# IN-12-Arduino-Shield.net
KiCad netlist of a schematic drawn in EAGLE
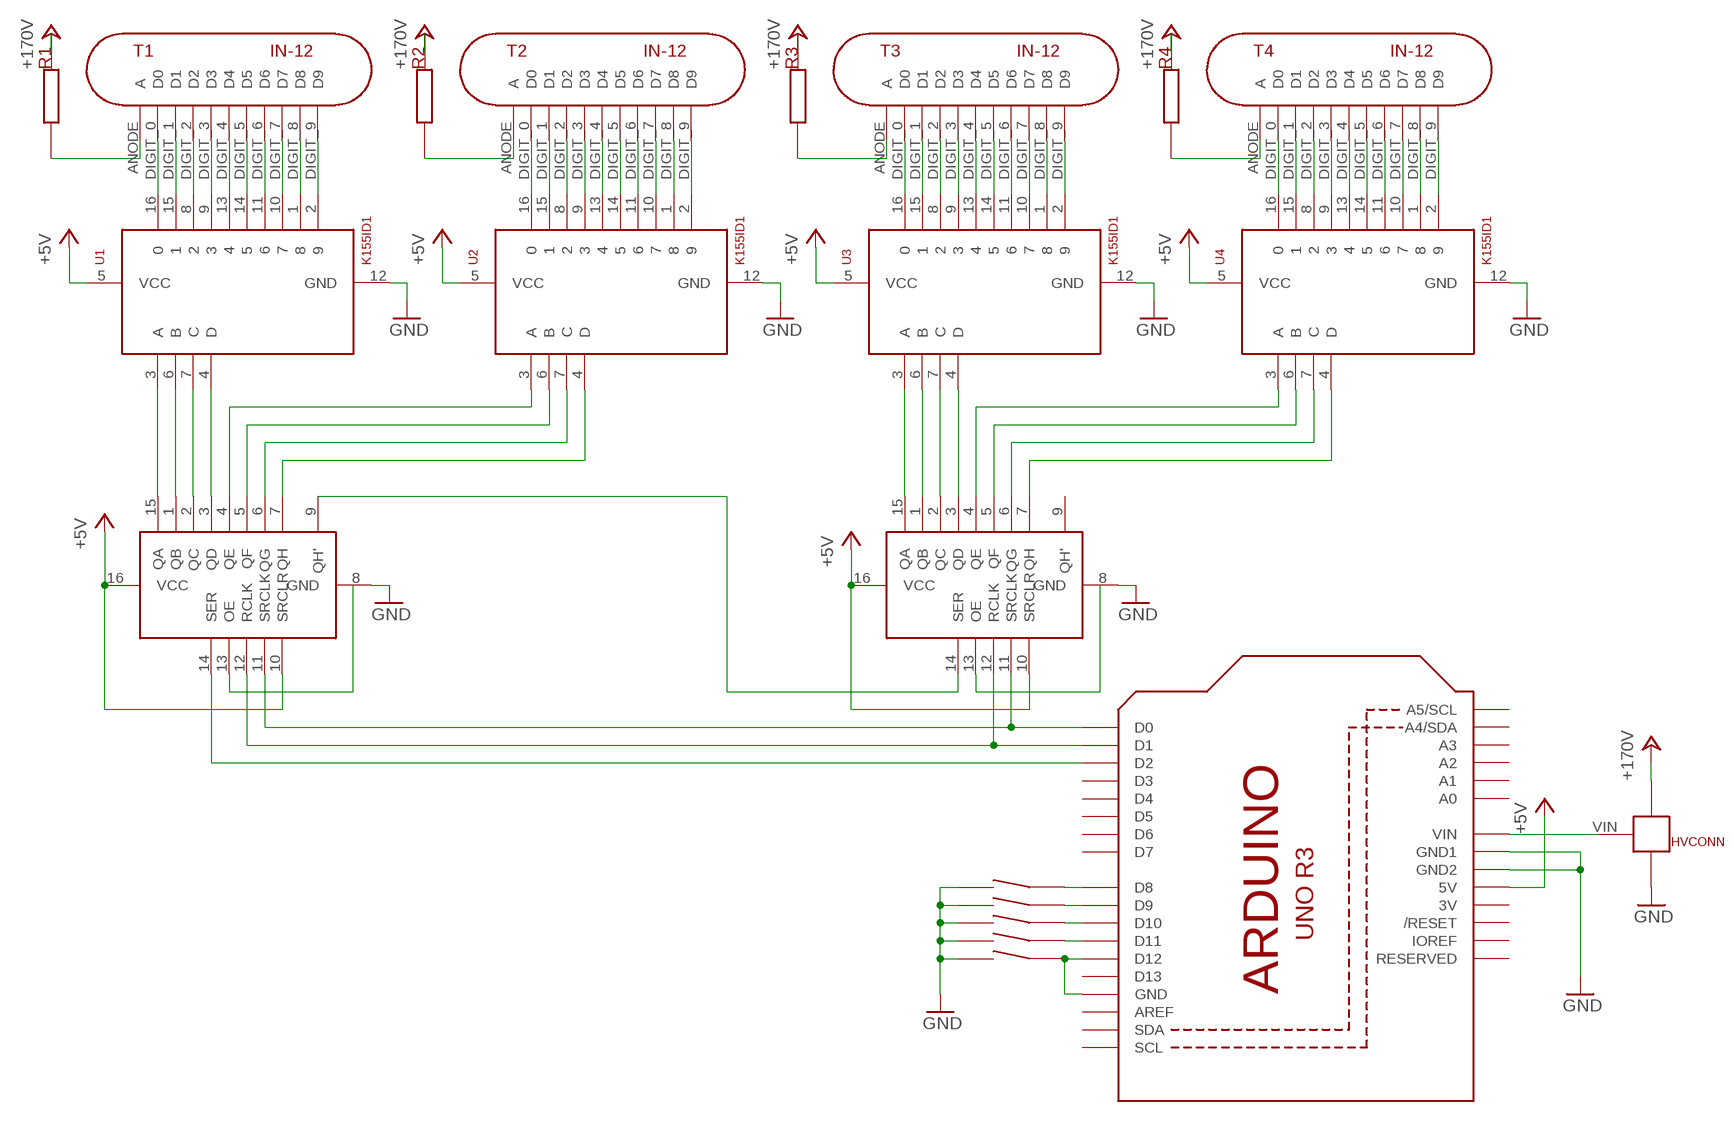
[diagram p0: schematic, sheet 1]

(export (version "E")
  (design (tool "Eeschema 10.0.6"))
  (components
    (comp (ref "HVCONN")
      (value "HV_CONNECTOR")
      (footprint "eagle-import:HV_CONNECTOR")
      (libsource (lib "eagle-import") (part "HV_CONNECTOR"))
    )
    (comp (ref "R1")
      (value "5,6K")
      (footprint "eagle-import:ANODE_RESISTOR")
      (libsource (lib "eagle-import") (part "ANODE_RESISTOR"))
    )
    (comp (ref "R2")
      (value "5,6K")
      (footprint "eagle-import:ANODE_RESISTOR")
      (libsource (lib "eagle-import") (part "ANODE_RESISTOR"))
    )
    (comp (ref "R3")
      (value "5,6K")
      (footprint "eagle-import:ANODE_RESISTOR")
      (libsource (lib "eagle-import") (part "ANODE_RESISTOR"))
    )
    (comp (ref "R4")
      (value "5,6K")
      (footprint "eagle-import:ANODE_RESISTOR")
      (libsource (lib "eagle-import") (part "ANODE_RESISTOR"))
    )
    (comp (ref "T1")
      (value "IN-12")
      (footprint "eagle-import:IN-12")
      (libsource (lib "eagle-import") (part "IN-12"))
    )
    (comp (ref "T2")
      (value "IN-12")
      (footprint "eagle-import:IN-12")
      (libsource (lib "eagle-import") (part "IN-12"))
    )
    (comp (ref "T3")
      (value "IN-12")
      (footprint "eagle-import:IN-12")
      (libsource (lib "eagle-import") (part "IN-12"))
    )
    (comp (ref "T4")
      (value "IN-12")
      (footprint "eagle-import:IN-12")
      (libsource (lib "eagle-import") (part "IN-12"))
    )
    (comp (ref "U$3")
      (value "PUSHBUTTON")
      (footprint "eagle-import:PUSHBUTTON")
      (libsource (lib "eagle-import") (part "PUSHBUTTON"))
    )
    (comp (ref "U$4")
      (value "PUSHBUTTON")
      (footprint "eagle-import:PUSHBUTTON")
      (libsource (lib "eagle-import") (part "PUSHBUTTON"))
    )
    (comp (ref "U$5")
      (value "PUSHBUTTON")
      (footprint "eagle-import:PUSHBUTTON")
      (libsource (lib "eagle-import") (part "PUSHBUTTON"))
    )
    (comp (ref "U$6")
      (value "PUSHBUTTON")
      (footprint "eagle-import:PUSHBUTTON")
      (libsource (lib "eagle-import") (part "PUSHBUTTON"))
    )
    (comp (ref "U$7")
      (value "PUSHBUTTON")
      (footprint "eagle-import:PUSHBUTTON")
      (libsource (lib "eagle-import") (part "PUSHBUTTON"))
    )
    (comp (ref "U1")
      (value "K155ID1")
      (footprint "eagle-import:DIP16-2.54-19.2X7.62MM")
      (libsource (lib "eagle-import") (part "K155ID1"))
    )
    (comp (ref "U2")
      (value "K155ID1")
      (footprint "eagle-import:DIP16-2.54-19.2X7.62MM")
      (libsource (lib "eagle-import") (part "K155ID1"))
    )
    (comp (ref "U3")
      (value "K155ID1")
      (footprint "eagle-import:DIP16-2.54-19.2X7.62MM")
      (libsource (lib "eagle-import") (part "K155ID1"))
    )
    (comp (ref "U4")
      (value "K155ID1")
      (footprint "eagle-import:DIP16-2.54-19.2X7.62MM")
      (libsource (lib "eagle-import") (part "K155ID1"))
    )
    (comp (ref "U5")
      (value "ARDUINOR3")
      (footprint "eagle-import:ARDUINOR3_NO_OUTLINE")
      (libsource (lib "eagle-import") (part "ARDUINOR3"))
    )
    (comp (ref "U6")
      (value "74HC595")
      (footprint "eagle-import:DIL16")
      (libsource (lib "eagle-import") (part "74HC595"))
    )
    (comp (ref "U7")
      (value "74HC595")
      (footprint "eagle-import:DIL16")
      (libsource (lib "eagle-import") (part "74HC595"))
    )
  )
  (nets
    (net (code "1") (name "+5V") (class "Default")
      (node (ref "U1") (pin "5") (pinfunction "VCC_5") (pintype "bidirectional"))
      (node (ref "U2") (pin "5") (pinfunction "VCC_5") (pintype "bidirectional"))
      (node (ref "U3") (pin "5") (pinfunction "VCC_5") (pintype "bidirectional"))
      (node (ref "U4") (pin "5") (pinfunction "VCC_5") (pintype "bidirectional"))
      (node (ref "U5") (pin "5V") (pinfunction "5V_5V") (pintype "power_in"))
      (node (ref "U6") (pin "10") (pinfunction "SRCLR_10") (pintype "bidirectional"))
      (node (ref "U6") (pin "16") (pinfunction "VCC_16") (pintype "bidirectional"))
      (node (ref "U7") (pin "10") (pinfunction "SRCLR_10") (pintype "bidirectional"))
      (node (ref "U7") (pin "16") (pinfunction "VCC_16") (pintype "bidirectional"))
    )
    (net (code "2") (name "+170V") (class "Default")
      (node (ref "HVCONN") (pin "+170V") (pinfunction "P$1_+170V") (pintype "bidirectional"))
      (node (ref "R1") (pin "P$2") (pinfunction "P$2_P$2") (pintype "bidirectional"))
      (node (ref "R2") (pin "P$2") (pinfunction "P$2_P$2") (pintype "bidirectional"))
      (node (ref "R3") (pin "P$2") (pinfunction "P$2_P$2") (pintype "bidirectional"))
      (node (ref "R4") (pin "P$2") (pinfunction "P$2_P$2") (pintype "bidirectional"))
    )
    (net (code "3") (name "/3V") (class "Default")
      (node (ref "U5") (pin "3V") (pinfunction "3V_3V") (pintype "power_in"))
    )
    (net (code "4") (name "GND") (class "Default")
      (node (ref "HVCONN") (pin "GND") (pinfunction "P$2_GND") (pintype "bidirectional"))
      (node (ref "U$3") (pin "P$1") (pinfunction "P$1_P$1") (pintype "bidirectional"))
      (node (ref "U$4") (pin "P$1") (pinfunction "P$1_P$1") (pintype "bidirectional"))
      (node (ref "U$5") (pin "P$1") (pinfunction "P$1_P$1") (pintype "bidirectional"))
      (node (ref "U$6") (pin "P$1") (pinfunction "P$1_P$1") (pintype "bidirectional"))
      (node (ref "U$7") (pin "P$1") (pinfunction "P$1_P$1") (pintype "bidirectional"))
      (node (ref "U1") (pin "12") (pinfunction "GND_12") (pintype "bidirectional"))
      (node (ref "U2") (pin "12") (pinfunction "GND_12") (pintype "bidirectional"))
      (node (ref "U3") (pin "12") (pinfunction "GND_12") (pintype "bidirectional"))
      (node (ref "U4") (pin "12") (pinfunction "GND_12") (pintype "bidirectional"))
      (node (ref "U5") (pin "GND1") (pinfunction "GND1_GND1") (pintype "power_in"))
      (node (ref "U5") (pin "GND2") (pinfunction "GND2_GND2") (pintype "power_in"))
      (node (ref "U6") (pin "8") (pinfunction "GND_8") (pintype "bidirectional"))
      (node (ref "U7") (pin "8") (pinfunction "GND_8") (pintype "bidirectional"))
    )
    (net (code "5") (name "Net-(HVCONN-PadVIN)") (class "Default")
      (node (ref "HVCONN") (pin "VIN") (pinfunction "VIN_VIN") (pintype "bidirectional"))
      (node (ref "U5") (pin "VIN") (pinfunction "VIN_VIN") (pintype "power_in"))
    )
    (net (code "6") (name "Net-(T1-A)") (class "Default")
      (node (ref "R1") (pin "P$1") (pinfunction "P$1_P$1") (pintype "bidirectional"))
      (node (ref "T1") (pin "ANODE") (pinfunction "A_ANODE") (pintype "bidirectional"))
    )
    (net (code "7") (name "Net-(T1-D0)") (class "Default")
      (node (ref "T1") (pin "DIGIT_0") (pinfunction "D0_DIGIT_0") (pintype "bidirectional"))
      (node (ref "U1") (pin "16") (pinfunction "0_16") (pintype "bidirectional"))
    )
    (net (code "8") (name "Net-(T1-D1)") (class "Default")
      (node (ref "T1") (pin "DIGIT_1") (pinfunction "D1_DIGIT_1") (pintype "bidirectional"))
      (node (ref "U1") (pin "15") (pinfunction "1_15") (pintype "bidirectional"))
    )
    (net (code "9") (name "Net-(T1-D2)") (class "Default")
      (node (ref "T1") (pin "DIGIT_2") (pinfunction "D2_DIGIT_2") (pintype "bidirectional"))
      (node (ref "U1") (pin "8") (pinfunction "2_8") (pintype "bidirectional"))
    )
    (net (code "10") (name "Net-(T1-D3)") (class "Default")
      (node (ref "T1") (pin "DIGIT_3") (pinfunction "D3_DIGIT_3") (pintype "bidirectional"))
      (node (ref "U1") (pin "9") (pinfunction "3_9") (pintype "bidirectional"))
    )
    (net (code "11") (name "Net-(T1-D4)") (class "Default")
      (node (ref "T1") (pin "DIGIT_4") (pinfunction "D4_DIGIT_4") (pintype "bidirectional"))
      (node (ref "U1") (pin "13") (pinfunction "4_13") (pintype "bidirectional"))
    )
    (net (code "12") (name "Net-(T1-D5)") (class "Default")
      (node (ref "T1") (pin "DIGIT_5") (pinfunction "D5_DIGIT_5") (pintype "bidirectional"))
      (node (ref "U1") (pin "14") (pinfunction "5_14") (pintype "bidirectional"))
    )
    (net (code "13") (name "Net-(T1-D6)") (class "Default")
      (node (ref "T1") (pin "DIGIT_6") (pinfunction "D6_DIGIT_6") (pintype "bidirectional"))
      (node (ref "U1") (pin "11") (pinfunction "6_11") (pintype "bidirectional"))
    )
    (net (code "14") (name "Net-(T1-D7)") (class "Default")
      (node (ref "T1") (pin "DIGIT_7") (pinfunction "D7_DIGIT_7") (pintype "bidirectional"))
      (node (ref "U1") (pin "10") (pinfunction "7_10") (pintype "bidirectional"))
    )
    (net (code "15") (name "Net-(T1-D8)") (class "Default")
      (node (ref "T1") (pin "DIGIT_8") (pinfunction "D8_DIGIT_8") (pintype "bidirectional"))
      (node (ref "U1") (pin "1") (pinfunction "8_1") (pintype "bidirectional"))
    )
    (net (code "16") (name "Net-(T1-D9)") (class "Default")
      (node (ref "T1") (pin "DIGIT_9") (pinfunction "D9_DIGIT_9") (pintype "bidirectional"))
      (node (ref "U1") (pin "2") (pinfunction "9_2") (pintype "bidirectional"))
    )
    (net (code "17") (name "Net-(T2-A)") (class "Default")
      (node (ref "R2") (pin "P$1") (pinfunction "P$1_P$1") (pintype "bidirectional"))
      (node (ref "T2") (pin "ANODE") (pinfunction "A_ANODE") (pintype "bidirectional"))
    )
    (net (code "18") (name "Net-(T2-D0)") (class "Default")
      (node (ref "T2") (pin "DIGIT_0") (pinfunction "D0_DIGIT_0") (pintype "bidirectional"))
      (node (ref "U2") (pin "16") (pinfunction "0_16") (pintype "bidirectional"))
    )
    (net (code "19") (name "Net-(T2-D1)") (class "Default")
      (node (ref "T2") (pin "DIGIT_1") (pinfunction "D1_DIGIT_1") (pintype "bidirectional"))
      (node (ref "U2") (pin "15") (pinfunction "1_15") (pintype "bidirectional"))
    )
    (net (code "20") (name "Net-(T2-D2)") (class "Default")
      (node (ref "T2") (pin "DIGIT_2") (pinfunction "D2_DIGIT_2") (pintype "bidirectional"))
      (node (ref "U2") (pin "8") (pinfunction "2_8") (pintype "bidirectional"))
    )
    (net (code "21") (name "Net-(T2-D3)") (class "Default")
      (node (ref "T2") (pin "DIGIT_3") (pinfunction "D3_DIGIT_3") (pintype "bidirectional"))
      (node (ref "U2") (pin "9") (pinfunction "3_9") (pintype "bidirectional"))
    )
    (net (code "22") (name "Net-(T2-D4)") (class "Default")
      (node (ref "T2") (pin "DIGIT_4") (pinfunction "D4_DIGIT_4") (pintype "bidirectional"))
      (node (ref "U2") (pin "13") (pinfunction "4_13") (pintype "bidirectional"))
    )
    (net (code "23") (name "Net-(T2-D5)") (class "Default")
      (node (ref "T2") (pin "DIGIT_5") (pinfunction "D5_DIGIT_5") (pintype "bidirectional"))
      (node (ref "U2") (pin "14") (pinfunction "5_14") (pintype "bidirectional"))
    )
    (net (code "24") (name "Net-(T2-D6)") (class "Default")
      (node (ref "T2") (pin "DIGIT_6") (pinfunction "D6_DIGIT_6") (pintype "bidirectional"))
      (node (ref "U2") (pin "11") (pinfunction "6_11") (pintype "bidirectional"))
    )
    (net (code "25") (name "Net-(T2-D7)") (class "Default")
      (node (ref "T2") (pin "DIGIT_7") (pinfunction "D7_DIGIT_7") (pintype "bidirectional"))
      (node (ref "U2") (pin "10") (pinfunction "7_10") (pintype "bidirectional"))
    )
    (net (code "26") (name "Net-(T2-D8)") (class "Default")
      (node (ref "T2") (pin "DIGIT_8") (pinfunction "D8_DIGIT_8") (pintype "bidirectional"))
      (node (ref "U2") (pin "1") (pinfunction "8_1") (pintype "bidirectional"))
    )
    (net (code "27") (name "Net-(T2-D9)") (class "Default")
      (node (ref "T2") (pin "DIGIT_9") (pinfunction "D9_DIGIT_9") (pintype "bidirectional"))
      (node (ref "U2") (pin "2") (pinfunction "9_2") (pintype "bidirectional"))
    )
    (net (code "28") (name "Net-(T3-A)") (class "Default")
      (node (ref "R3") (pin "P$1") (pinfunction "P$1_P$1") (pintype "bidirectional"))
      (node (ref "T3") (pin "ANODE") (pinfunction "A_ANODE") (pintype "bidirectional"))
    )
    (net (code "29") (name "Net-(T3-D0)") (class "Default")
      (node (ref "T3") (pin "DIGIT_0") (pinfunction "D0_DIGIT_0") (pintype "bidirectional"))
      (node (ref "U3") (pin "16") (pinfunction "0_16") (pintype "bidirectional"))
    )
    (net (code "30") (name "Net-(T3-D1)") (class "Default")
      (node (ref "T3") (pin "DIGIT_1") (pinfunction "D1_DIGIT_1") (pintype "bidirectional"))
      (node (ref "U3") (pin "15") (pinfunction "1_15") (pintype "bidirectional"))
    )
    (net (code "31") (name "Net-(T3-D2)") (class "Default")
      (node (ref "T3") (pin "DIGIT_2") (pinfunction "D2_DIGIT_2") (pintype "bidirectional"))
      (node (ref "U3") (pin "8") (pinfunction "2_8") (pintype "bidirectional"))
    )
    (net (code "32") (name "Net-(T3-D3)") (class "Default")
      (node (ref "T3") (pin "DIGIT_3") (pinfunction "D3_DIGIT_3") (pintype "bidirectional"))
      (node (ref "U3") (pin "9") (pinfunction "3_9") (pintype "bidirectional"))
    )
    (net (code "33") (name "Net-(T3-D4)") (class "Default")
      (node (ref "T3") (pin "DIGIT_4") (pinfunction "D4_DIGIT_4") (pintype "bidirectional"))
      (node (ref "U3") (pin "13") (pinfunction "4_13") (pintype "bidirectional"))
    )
    (net (code "34") (name "Net-(T3-D5)") (class "Default")
      (node (ref "T3") (pin "DIGIT_5") (pinfunction "D5_DIGIT_5") (pintype "bidirectional"))
      (node (ref "U3") (pin "14") (pinfunction "5_14") (pintype "bidirectional"))
    )
    (net (code "35") (name "Net-(T3-D6)") (class "Default")
      (node (ref "T3") (pin "DIGIT_6") (pinfunction "D6_DIGIT_6") (pintype "bidirectional"))
      (node (ref "U3") (pin "11") (pinfunction "6_11") (pintype "bidirectional"))
    )
    (net (code "36") (name "Net-(T3-D7)") (class "Default")
      (node (ref "T3") (pin "DIGIT_7") (pinfunction "D7_DIGIT_7") (pintype "bidirectional"))
      (node (ref "U3") (pin "10") (pinfunction "7_10") (pintype "bidirectional"))
    )
    (net (code "37") (name "Net-(T3-D8)") (class "Default")
      (node (ref "T3") (pin "DIGIT_8") (pinfunction "D8_DIGIT_8") (pintype "bidirectional"))
      (node (ref "U3") (pin "1") (pinfunction "8_1") (pintype "bidirectional"))
    )
    (net (code "38") (name "Net-(T3-D9)") (class "Default")
      (node (ref "T3") (pin "DIGIT_9") (pinfunction "D9_DIGIT_9") (pintype "bidirectional"))
      (node (ref "U3") (pin "2") (pinfunction "9_2") (pintype "bidirectional"))
    )
    (net (code "39") (name "Net-(T4-A)") (class "Default")
      (node (ref "R4") (pin "P$1") (pinfunction "P$1_P$1") (pintype "bidirectional"))
      (node (ref "T4") (pin "ANODE") (pinfunction "A_ANODE") (pintype "bidirectional"))
    )
    (net (code "40") (name "Net-(T4-D0)") (class "Default")
      (node (ref "T4") (pin "DIGIT_0") (pinfunction "D0_DIGIT_0") (pintype "bidirectional"))
      (node (ref "U4") (pin "16") (pinfunction "0_16") (pintype "bidirectional"))
    )
    (net (code "41") (name "Net-(T4-D1)") (class "Default")
      (node (ref "T4") (pin "DIGIT_1") (pinfunction "D1_DIGIT_1") (pintype "bidirectional"))
      (node (ref "U4") (pin "15") (pinfunction "1_15") (pintype "bidirectional"))
    )
    (net (code "42") (name "Net-(T4-D2)") (class "Default")
      (node (ref "T4") (pin "DIGIT_2") (pinfunction "D2_DIGIT_2") (pintype "bidirectional"))
      (node (ref "U4") (pin "8") (pinfunction "2_8") (pintype "bidirectional"))
    )
    (net (code "43") (name "Net-(T4-D3)") (class "Default")
      (node (ref "T4") (pin "DIGIT_3") (pinfunction "D3_DIGIT_3") (pintype "bidirectional"))
      (node (ref "U4") (pin "9") (pinfunction "3_9") (pintype "bidirectional"))
    )
    (net (code "44") (name "Net-(T4-D4)") (class "Default")
      (node (ref "T4") (pin "DIGIT_4") (pinfunction "D4_DIGIT_4") (pintype "bidirectional"))
      (node (ref "U4") (pin "13") (pinfunction "4_13") (pintype "bidirectional"))
    )
    (net (code "45") (name "Net-(T4-D5)") (class "Default")
      (node (ref "T4") (pin "DIGIT_5") (pinfunction "D5_DIGIT_5") (pintype "bidirectional"))
      (node (ref "U4") (pin "14") (pinfunction "5_14") (pintype "bidirectional"))
    )
    (net (code "46") (name "Net-(T4-D6)") (class "Default")
      (node (ref "T4") (pin "DIGIT_6") (pinfunction "D6_DIGIT_6") (pintype "bidirectional"))
      (node (ref "U4") (pin "11") (pinfunction "6_11") (pintype "bidirectional"))
    )
    (net (code "47") (name "Net-(T4-D7)") (class "Default")
      (node (ref "T4") (pin "DIGIT_7") (pinfunction "D7_DIGIT_7") (pintype "bidirectional"))
      (node (ref "U4") (pin "10") (pinfunction "7_10") (pintype "bidirectional"))
    )
    (net (code "48") (name "Net-(T4-D8)") (class "Default")
      (node (ref "T4") (pin "DIGIT_8") (pinfunction "D8_DIGIT_8") (pintype "bidirectional"))
      (node (ref "U4") (pin "1") (pinfunction "8_1") (pintype "bidirectional"))
    )
    (net (code "49") (name "Net-(T4-D9)") (class "Default")
      (node (ref "T4") (pin "DIGIT_9") (pinfunction "D9_DIGIT_9") (pintype "bidirectional"))
      (node (ref "U4") (pin "2") (pinfunction "9_2") (pintype "bidirectional"))
    )
    (net (code "50") (name "Net-(U$3-PadP$2)") (class "Default")
      (node (ref "U$3") (pin "P$2") (pinfunction "P$2_P$2") (pintype "bidirectional"))
      (node (ref "U5") (pin "D12") (pinfunction "D12_D12") (pintype "bidirectional"))
      (node (ref "U5") (pin "GND") (pinfunction "GND_GND") (pintype "power_in"))
    )
    (net (code "51") (name "Net-(U$4-PadP$2)") (class "Default")
      (node (ref "U$4") (pin "P$2") (pinfunction "P$2_P$2") (pintype "bidirectional"))
      (node (ref "U5") (pin "D8") (pinfunction "D8_D8") (pintype "bidirectional"))
    )
    (net (code "52") (name "Net-(U$5-PadP$2)") (class "Default")
      (node (ref "U$5") (pin "P$2") (pinfunction "P$2_P$2") (pintype "bidirectional"))
      (node (ref "U5") (pin "D9") (pinfunction "D9_D9") (pintype "bidirectional"))
    )
    (net (code "53") (name "Net-(U$6-PadP$2)") (class "Default")
      (node (ref "U$6") (pin "P$2") (pinfunction "P$2_P$2") (pintype "bidirectional"))
      (node (ref "U5") (pin "D10") (pinfunction "D10_D10") (pintype "bidirectional"))
    )
    (net (code "54") (name "Net-(U$7-PadP$2)") (class "Default")
      (node (ref "U$7") (pin "P$2") (pinfunction "P$2_P$2") (pintype "bidirectional"))
      (node (ref "U5") (pin "D11") (pinfunction "D11_D11") (pintype "bidirectional"))
    )
    (net (code "55") (name "Net-(U1-A)") (class "Default")
      (node (ref "U1") (pin "3") (pinfunction "A_3") (pintype "bidirectional"))
      (node (ref "U6") (pin "15") (pinfunction "QA_15") (pintype "bidirectional"))
    )
    (net (code "56") (name "Net-(U1-B)") (class "Default")
      (node (ref "U1") (pin "6") (pinfunction "B_6") (pintype "bidirectional"))
      (node (ref "U6") (pin "1") (pinfunction "QB_1") (pintype "bidirectional"))
    )
    (net (code "57") (name "Net-(U1-C)") (class "Default")
      (node (ref "U1") (pin "7") (pinfunction "C_7") (pintype "bidirectional"))
      (node (ref "U6") (pin "2") (pinfunction "QC_2") (pintype "bidirectional"))
    )
    (net (code "58") (name "Net-(U1-D)") (class "Default")
      (node (ref "U1") (pin "4") (pinfunction "D_4") (pintype "bidirectional"))
      (node (ref "U6") (pin "3") (pinfunction "QD_3") (pintype "bidirectional"))
    )
    (net (code "59") (name "Net-(U2-A)") (class "Default")
      (node (ref "U2") (pin "3") (pinfunction "A_3") (pintype "bidirectional"))
      (node (ref "U6") (pin "4") (pinfunction "QE_4") (pintype "bidirectional"))
    )
    (net (code "60") (name "Net-(U2-B)") (class "Default")
      (node (ref "U2") (pin "6") (pinfunction "B_6") (pintype "bidirectional"))
      (node (ref "U6") (pin "5") (pinfunction "QF_5") (pintype "bidirectional"))
    )
    (net (code "61") (name "Net-(U2-C)") (class "Default")
      (node (ref "U2") (pin "7") (pinfunction "C_7") (pintype "bidirectional"))
      (node (ref "U6") (pin "6") (pinfunction "QG_6") (pintype "bidirectional"))
    )
    (net (code "62") (name "Net-(U2-D)") (class "Default")
      (node (ref "U2") (pin "4") (pinfunction "D_4") (pintype "bidirectional"))
      (node (ref "U6") (pin "7") (pinfunction "QH_7") (pintype "bidirectional"))
    )
    (net (code "63") (name "Net-(U3-A)") (class "Default")
      (node (ref "U3") (pin "3") (pinfunction "A_3") (pintype "bidirectional"))
      (node (ref "U7") (pin "15") (pinfunction "QA_15") (pintype "bidirectional"))
    )
    (net (code "64") (name "Net-(U3-B)") (class "Default")
      (node (ref "U3") (pin "6") (pinfunction "B_6") (pintype "bidirectional"))
      (node (ref "U7") (pin "1") (pinfunction "QB_1") (pintype "bidirectional"))
    )
    (net (code "65") (name "Net-(U3-C)") (class "Default")
      (node (ref "U3") (pin "7") (pinfunction "C_7") (pintype "bidirectional"))
      (node (ref "U7") (pin "2") (pinfunction "QC_2") (pintype "bidirectional"))
    )
    (net (code "66") (name "Net-(U3-D)") (class "Default")
      (node (ref "U3") (pin "4") (pinfunction "D_4") (pintype "bidirectional"))
      (node (ref "U7") (pin "3") (pinfunction "QD_3") (pintype "bidirectional"))
    )
    (net (code "67") (name "Net-(U4-A)") (class "Default")
      (node (ref "U4") (pin "3") (pinfunction "A_3") (pintype "bidirectional"))
      (node (ref "U7") (pin "4") (pinfunction "QE_4") (pintype "bidirectional"))
    )
    (net (code "68") (name "Net-(U4-B)") (class "Default")
      (node (ref "U4") (pin "6") (pinfunction "B_6") (pintype "bidirectional"))
      (node (ref "U7") (pin "5") (pinfunction "QF_5") (pintype "bidirectional"))
    )
    (net (code "69") (name "Net-(U4-C)") (class "Default")
      (node (ref "U4") (pin "7") (pinfunction "C_7") (pintype "bidirectional"))
      (node (ref "U7") (pin "6") (pinfunction "QG_6") (pintype "bidirectional"))
    )
    (net (code "70") (name "Net-(U4-D)") (class "Default")
      (node (ref "U4") (pin "4") (pinfunction "D_4") (pintype "bidirectional"))
      (node (ref "U7") (pin "7") (pinfunction "QH_7") (pintype "bidirectional"))
    )
    (net (code "71") (name "Net-(U6-QH')") (class "Default")
      (node (ref "U6") (pin "9") (pinfunction "QH'_9") (pintype "bidirectional"))
      (node (ref "U7") (pin "14") (pinfunction "SER_14") (pintype "bidirectional"))
    )
    (net (code "72") (name "Net-(U6-RCLK)") (class "Default")
      (node (ref "U5") (pin "D1") (pinfunction "D1_D1") (pintype "bidirectional"))
      (node (ref "U6") (pin "12") (pinfunction "RCLK_12") (pintype "bidirectional"))
      (node (ref "U7") (pin "12") (pinfunction "RCLK_12") (pintype "bidirectional"))
    )
    (net (code "73") (name "Net-(U6-SER)") (class "Default")
      (node (ref "U5") (pin "D2") (pinfunction "D2_D2") (pintype "bidirectional"))
      (node (ref "U6") (pin "14") (pinfunction "SER_14") (pintype "bidirectional"))
    )
    (net (code "74") (name "Net-(U6-SRCLK)") (class "Default")
      (node (ref "U5") (pin "D0") (pinfunction "D0_D0") (pintype "bidirectional"))
      (node (ref "U6") (pin "11") (pinfunction "SRCLK_11") (pintype "bidirectional"))
      (node (ref "U7") (pin "11") (pinfunction "SRCLK_11") (pintype "bidirectional"))
    )
    (net (code "75") (name "unconnected-(U5-A4{slash}SDA-PadA4)") (class "Default")
      (node (ref "U5") (pin "A4") (pinfunction "A4/SDA_A4") (pintype "bidirectional"))
    )
    (net (code "76") (name "unconnected-(U5-A5{slash}SCL-PadA5)") (class "Default")
      (node (ref "U5") (pin "A5") (pinfunction "A5/SCL_A5") (pintype "bidirectional"))
    )
    (net (code "77") (name "unconnected-(U5-PadA0)") (class "Default")
      (node (ref "U5") (pin "A0") (pinfunction "A0_A0") (pintype "bidirectional"))
    )
    (net (code "78") (name "unconnected-(U5-PadA1)") (class "Default")
      (node (ref "U5") (pin "A1") (pinfunction "A1_A1") (pintype "bidirectional"))
    )
    (net (code "79") (name "unconnected-(U5-PadA2)") (class "Default")
      (node (ref "U5") (pin "A2") (pinfunction "A2_A2") (pintype "bidirectional"))
    )
    (net (code "80") (name "unconnected-(U5-PadA3)") (class "Default")
      (node (ref "U5") (pin "A3") (pinfunction "A3_A3") (pintype "bidirectional"))
    )
    (net (code "81") (name "unconnected-(U5-PadAREF)") (class "Default")
      (node (ref "U5") (pin "AREF") (pinfunction "AREF_AREF") (pintype "bidirectional"))
    )
    (net (code "82") (name "unconnected-(U5-PadD3)") (class "Default")
      (node (ref "U5") (pin "D3") (pinfunction "D3_D3") (pintype "bidirectional"))
    )
    (net (code "83") (name "unconnected-(U5-PadD4)") (class "Default")
      (node (ref "U5") (pin "D4") (pinfunction "D4_D4") (pintype "bidirectional"))
    )
    (net (code "84") (name "unconnected-(U5-PadD5)") (class "Default")
      (node (ref "U5") (pin "D5") (pinfunction "D5_D5") (pintype "bidirectional"))
    )
    (net (code "85") (name "unconnected-(U5-PadD6)") (class "Default")
      (node (ref "U5") (pin "D6") (pinfunction "D6_D6") (pintype "bidirectional"))
    )
    (net (code "86") (name "unconnected-(U5-PadD7)") (class "Default")
      (node (ref "U5") (pin "D7") (pinfunction "D7_D7") (pintype "bidirectional"))
    )
    (net (code "87") (name "unconnected-(U5-PadD13)") (class "Default")
      (node (ref "U5") (pin "D13") (pinfunction "D13_D13") (pintype "bidirectional"))
    )
    (net (code "88") (name "unconnected-(U5-PadIOREF)") (class "Default")
      (node (ref "U5") (pin "IOREF") (pinfunction "IOREF_IOREF") (pintype "output"))
    )
    (net (code "89") (name "unconnected-(U5-PadRESERVED)") (class "Default")
      (node (ref "U5") (pin "RESERVED") (pinfunction "RESERVED_RESERVED") (pintype "no_connect"))
    )
    (net (code "90") (name "unconnected-(U5-PadSCL)") (class "Default")
      (node (ref "U5") (pin "SCL") (pinfunction "SCL_SCL") (pintype "bidirectional"))
    )
    (net (code "91") (name "unconnected-(U5-PadSDA)") (class "Default")
      (node (ref "U5") (pin "SDA") (pinfunction "SDA_SDA") (pintype "bidirectional"))
    )
    (net (code "92") (name "unconnected-(U5-{slash}RESET-PadRESET)") (class "Default")
      (node (ref "U5") (pin "RESET") (pinfunction "/RESET_RESET") (pintype "bidirectional"))
    )
    (net (code "93") (name "unconnected-(U6-OE-Pad13)") (class "Default")
      (node (ref "U6") (pin "13") (pinfunction "OE_13") (pintype "bidirectional"))
    )
    (net (code "94") (name "unconnected-(U7-OE-Pad13)") (class "Default")
      (node (ref "U7") (pin "13") (pinfunction "OE_13") (pintype "bidirectional"))
    )
    (net (code "95") (name "unconnected-(U7-QH'-Pad9)") (class "Default")
      (node (ref "U7") (pin "9") (pinfunction "QH'_9") (pintype "bidirectional"))
    )
  )
)
